# 09_Connectors_STM32_B.net
KiCad netlist of a schematic drawn in Altium Designer
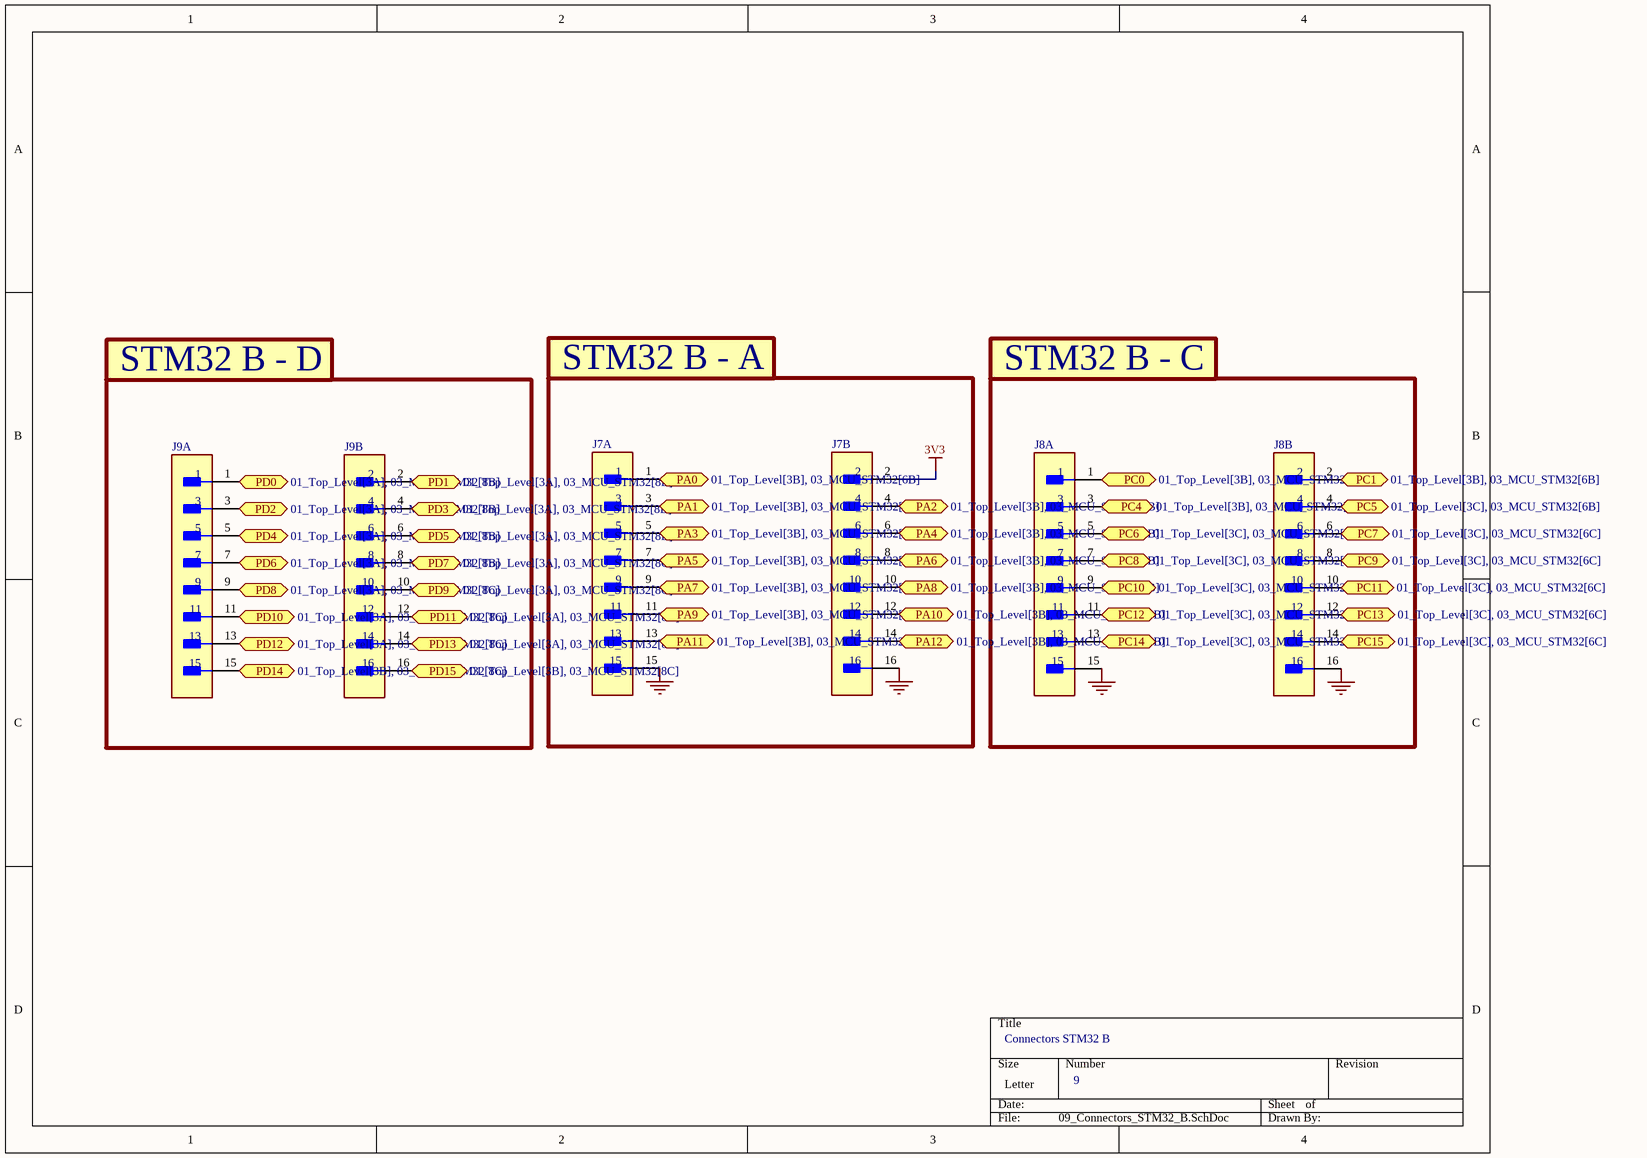
[diagram p0: 09_Connectors_STM32_B.SchDoc]

(export (version "E")
  (design (tool "Eeschema 10.0.6"))
  (components
    (comp (ref "J7")
      (value "GRPB082MWCN-RC")
      (footprint "FP-GRPB082MWCN-RC-MFG")
      (description "CONN HEADER R/A 16POS 1.27MM")
      (libsource (lib "Altium Content Vault") (part "ecabc7128bd599dbeade09ffe984aba"))
    )
    (comp (ref "J8")
      (value "GRPB082MWCN-RC")
      (footprint "FP-GRPB082MWCN-RC-MFG")
      (description "CONN HEADER R/A 16POS 1.27MM")
      (libsource (lib "Altium Content Vault") (part "ecabc7128bd599dbeade09ffe984aba"))
    )
    (comp (ref "J9")
      (value "GRPB082MWCN-RC")
      (footprint "FP-GRPB082MWCN-RC-MFG")
      (description "CONN HEADER R/A 16POS 1.27MM")
      (libsource (lib "Altium Content Vault") (part "ecabc7128bd599dbeade09ffe984aba"))
    )
  )
  (nets
    (net (code "1") (name "/PA0") (class "Default")
      (node (ref "J7") (pin "1") (pinfunction "1_1") (pintype "passive"))
    )
    (net (code "2") (name "/PA1") (class "Default")
      (node (ref "J7") (pin "3") (pinfunction "3_3") (pintype "passive"))
    )
    (net (code "3") (name "/PA2") (class "Default")
      (node (ref "J7") (pin "4") (pinfunction "4_4") (pintype "passive"))
    )
    (net (code "4") (name "/PA3") (class "Default")
      (node (ref "J7") (pin "5") (pinfunction "5_5") (pintype "passive"))
    )
    (net (code "5") (name "/PA4") (class "Default")
      (node (ref "J7") (pin "6") (pinfunction "6_6") (pintype "passive"))
    )
    (net (code "6") (name "/PA5") (class "Default")
      (node (ref "J7") (pin "7") (pinfunction "7_7") (pintype "passive"))
    )
    (net (code "7") (name "/PA6") (class "Default")
      (node (ref "J7") (pin "8") (pinfunction "8_8") (pintype "passive"))
    )
    (net (code "8") (name "/PA7") (class "Default")
      (node (ref "J7") (pin "9") (pinfunction "9_9") (pintype "passive"))
    )
    (net (code "9") (name "/PA8") (class "Default")
      (node (ref "J7") (pin "10") (pinfunction "10_10") (pintype "passive"))
    )
    (net (code "10") (name "/PA9") (class "Default")
      (node (ref "J7") (pin "11") (pinfunction "11_11") (pintype "passive"))
    )
    (net (code "11") (name "/PA10") (class "Default")
      (node (ref "J7") (pin "12") (pinfunction "12_12") (pintype "passive"))
    )
    (net (code "12") (name "/PA11") (class "Default")
      (node (ref "J7") (pin "13") (pinfunction "13_13") (pintype "passive"))
    )
    (net (code "13") (name "/PA12") (class "Default")
      (node (ref "J7") (pin "14") (pinfunction "14_14") (pintype "passive"))
    )
    (net (code "14") (name "/PC0") (class "Default")
      (node (ref "J8") (pin "1") (pinfunction "1_1") (pintype "passive"))
    )
    (net (code "15") (name "/PC1") (class "Default")
      (node (ref "J8") (pin "2") (pinfunction "2_2") (pintype "passive"))
    )
    (net (code "16") (name "/PC4") (class "Default")
      (node (ref "J8") (pin "3") (pinfunction "3_3") (pintype "passive"))
    )
    (net (code "17") (name "/PC5") (class "Default")
      (node (ref "J8") (pin "4") (pinfunction "4_4") (pintype "passive"))
    )
    (net (code "18") (name "/PC6") (class "Default")
      (node (ref "J8") (pin "5") (pinfunction "5_5") (pintype "passive"))
    )
    (net (code "19") (name "/PC7") (class "Default")
      (node (ref "J8") (pin "6") (pinfunction "6_6") (pintype "passive"))
    )
    (net (code "20") (name "/PC8") (class "Default")
      (node (ref "J8") (pin "7") (pinfunction "7_7") (pintype "passive"))
    )
    (net (code "21") (name "/PC9") (class "Default")
      (node (ref "J8") (pin "8") (pinfunction "8_8") (pintype "passive"))
    )
    (net (code "22") (name "/PC10") (class "Default")
      (node (ref "J8") (pin "9") (pinfunction "9_9") (pintype "passive"))
    )
    (net (code "23") (name "/PC11") (class "Default")
      (node (ref "J8") (pin "10") (pinfunction "10_10") (pintype "passive"))
    )
    (net (code "24") (name "/PC12") (class "Default")
      (node (ref "J8") (pin "11") (pinfunction "11_11") (pintype "passive"))
    )
    (net (code "25") (name "/PC13") (class "Default")
      (node (ref "J8") (pin "12") (pinfunction "12_12") (pintype "passive"))
    )
    (net (code "26") (name "/PC14") (class "Default")
      (node (ref "J8") (pin "13") (pinfunction "13_13") (pintype "passive"))
    )
    (net (code "27") (name "/PC15") (class "Default")
      (node (ref "J8") (pin "14") (pinfunction "14_14") (pintype "passive"))
    )
    (net (code "28") (name "/PD0") (class "Default")
      (node (ref "J9") (pin "1") (pinfunction "1_1") (pintype "passive"))
    )
    (net (code "29") (name "/PD1") (class "Default")
      (node (ref "J9") (pin "2") (pinfunction "2_2") (pintype "passive"))
    )
    (net (code "30") (name "/PD2") (class "Default")
      (node (ref "J9") (pin "3") (pinfunction "3_3") (pintype "passive"))
    )
    (net (code "31") (name "/PD3") (class "Default")
      (node (ref "J9") (pin "4") (pinfunction "4_4") (pintype "passive"))
    )
    (net (code "32") (name "/PD4") (class "Default")
      (node (ref "J9") (pin "5") (pinfunction "5_5") (pintype "passive"))
    )
    (net (code "33") (name "/PD5") (class "Default")
      (node (ref "J9") (pin "6") (pinfunction "6_6") (pintype "passive"))
    )
    (net (code "34") (name "/PD6") (class "Default")
      (node (ref "J9") (pin "7") (pinfunction "7_7") (pintype "passive"))
    )
    (net (code "35") (name "/PD7") (class "Default")
      (node (ref "J9") (pin "8") (pinfunction "8_8") (pintype "passive"))
    )
    (net (code "36") (name "/PD8") (class "Default")
      (node (ref "J9") (pin "9") (pinfunction "9_9") (pintype "passive"))
    )
    (net (code "37") (name "/PD9") (class "Default")
      (node (ref "J9") (pin "10") (pinfunction "10_10") (pintype "passive"))
    )
    (net (code "38") (name "/PD10") (class "Default")
      (node (ref "J9") (pin "11") (pinfunction "11_11") (pintype "passive"))
    )
    (net (code "39") (name "/PD11") (class "Default")
      (node (ref "J9") (pin "12") (pinfunction "12_12") (pintype "passive"))
    )
    (net (code "40") (name "/PD12") (class "Default")
      (node (ref "J9") (pin "13") (pinfunction "13_13") (pintype "passive"))
    )
    (net (code "41") (name "/PD13") (class "Default")
      (node (ref "J9") (pin "14") (pinfunction "14_14") (pintype "passive"))
    )
    (net (code "42") (name "/PD14") (class "Default")
      (node (ref "J9") (pin "15") (pinfunction "15_15") (pintype "passive"))
    )
    (net (code "43") (name "/PD15") (class "Default")
      (node (ref "J9") (pin "16") (pinfunction "16_16") (pintype "passive"))
    )
    (net (code "44") (name "3V3") (class "Default")
      (node (ref "J7") (pin "2") (pinfunction "2_2") (pintype "passive"))
    )
    (net (code "45") (name "GND") (class "Default")
      (node (ref "J7") (pin "15") (pinfunction "15_15") (pintype "passive"))
      (node (ref "J7") (pin "16") (pinfunction "16_16") (pintype "passive"))
      (node (ref "J8") (pin "15") (pinfunction "15_15") (pintype "passive"))
      (node (ref "J8") (pin "16") (pinfunction "16_16") (pintype "passive"))
    )
  )
)
